# symbol.net
KiCad netlist of a schematic drawn in Altium Designer
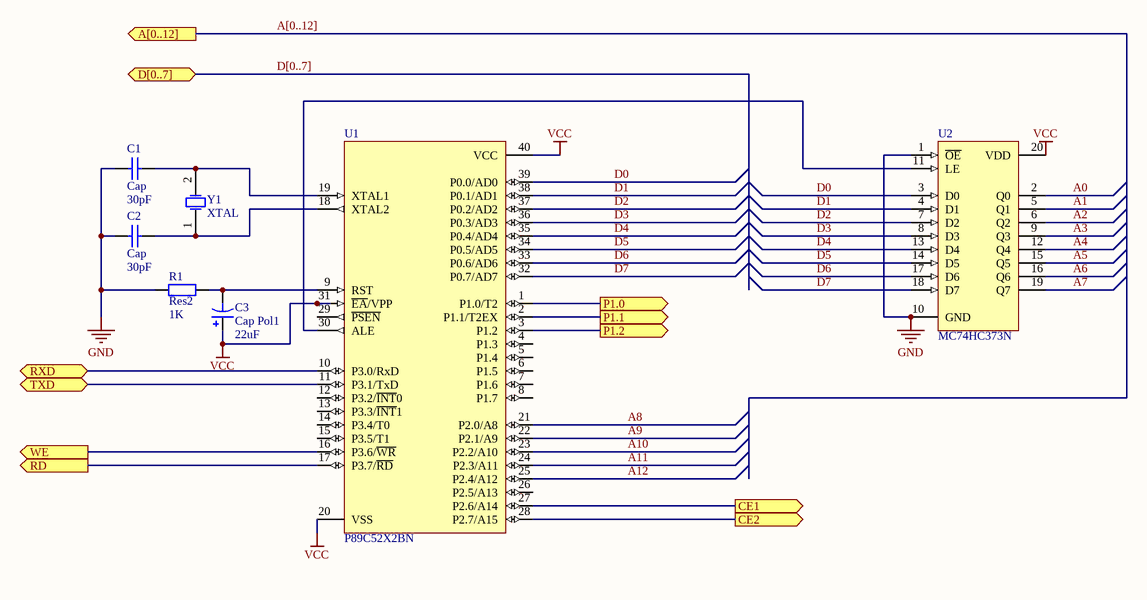
[diagram p0: 单片机系统电路symbol.SchDoc]

(export (version "E")
  (design (tool "Eeschema 10.0.6"))
  (components
    (comp (ref "C1")
      (value "Cap")
      (footprint "RAD-0.3")
      (description "Capacitor")
      (fields (field (name "ALTIUM_VALUE") "30pF") (field (name "PUBLISHER") "Altium Limited"))
      (libsource (lib "Miscellaneous Devices") (part "Cap"))
    )
    (comp (ref "C2")
      (value "Cap")
      (footprint "RAD-0.3")
      (description "Capacitor")
      (fields (field (name "ALTIUM_VALUE") "30pF") (field (name "PUBLISHER") "Altium Limited"))
      (libsource (lib "Miscellaneous Devices") (part "Cap"))
    )
    (comp (ref "C3")
      (value "Cap Pol1")
      (footprint "RB7.6-15")
      (description "Polarized Capacitor (Radial)")
      (fields (field (name "ALTIUM_VALUE") "22uF") (field (name "PUBLISHER") "Altium Limited"))
      (libsource (lib "Miscellaneous Devices") (part "Cap Pol1"))
    )
    (comp (ref "R1")
      (value "Res2")
      (footprint "AXIAL-0.4")
      (description "Resistor")
      (fields (field (name "ALTIUM_VALUE") "1K") (field (name "PUBLISHER") "Altium Limited"))
      (libsource (lib "Miscellaneous Devices") (part "Res2"))
    )
    (comp (ref "U1")
      (value "P89C52X2BN")
      (footprint "SOT129-1")
      (description "80C51 8-Bit Flash Microcontroller Family, 8 kB Flash")
      (fields (field (name "PUBLISHER") "Altium Limited"))
      (libsource (lib "Philips Microcontroller 8-Bit") (part "P89C52X2BN"))
    )
    (comp (ref "U2")
      (value "MC74HC373N")
      (footprint "738-03")
      (description "Octal 3-State Non-Inverting Transparent Latch")
      (fields (field (name "PUBLISHER") "Altium Limited"))
      (libsource (lib "Motorola Logic Latch") (part "MC74HC373N"))
    )
    (comp (ref "Y1")
      (value "XTAL")
      (footprint "R38")
      (description "Crystal Oscillator")
      (fields (field (name "PUBLISHER") "Altium Limited"))
      (libsource (lib "Miscellaneous Devices") (part "XTAL"))
    )
  )
  (nets
    (net (code "1") (name "/A0") (class "Default")
      (node (ref "U2") (pin "2") (pinfunction "Q0_2") (pintype "tri_state"))
    )
    (net (code "2") (name "/A1") (class "Default")
      (node (ref "U2") (pin "5") (pinfunction "Q1_5") (pintype "tri_state"))
    )
    (net (code "3") (name "/A2") (class "Default")
      (node (ref "U2") (pin "6") (pinfunction "Q2_6") (pintype "tri_state"))
    )
    (net (code "4") (name "/A3") (class "Default")
      (node (ref "U2") (pin "9") (pinfunction "Q3_9") (pintype "tri_state"))
    )
    (net (code "5") (name "/A4") (class "Default")
      (node (ref "U2") (pin "12") (pinfunction "Q4_12") (pintype "tri_state"))
    )
    (net (code "6") (name "/A5") (class "Default")
      (node (ref "U2") (pin "15") (pinfunction "Q5_15") (pintype "tri_state"))
    )
    (net (code "7") (name "/A6") (class "Default")
      (node (ref "U2") (pin "16") (pinfunction "Q6_16") (pintype "tri_state"))
    )
    (net (code "8") (name "/A7") (class "Default")
      (node (ref "U2") (pin "19") (pinfunction "Q7_19") (pintype "tri_state"))
    )
    (net (code "9") (name "/A8") (class "Default")
      (node (ref "U1") (pin "21") (pinfunction "P2.0/A8_21") (pintype "bidirectional"))
    )
    (net (code "10") (name "/A9") (class "Default")
      (node (ref "U1") (pin "22") (pinfunction "P2.1/A9_22") (pintype "bidirectional"))
    )
    (net (code "11") (name "/A10") (class "Default")
      (node (ref "U1") (pin "23") (pinfunction "P2.2/A10_23") (pintype "bidirectional"))
    )
    (net (code "12") (name "/A11") (class "Default")
      (node (ref "U1") (pin "24") (pinfunction "P2.3/A11_24") (pintype "bidirectional"))
    )
    (net (code "13") (name "/A12") (class "Default")
      (node (ref "U1") (pin "25") (pinfunction "P2.4/A12_25") (pintype "bidirectional"))
    )
    (net (code "15") (name "/CE1") (class "Default")
      (node (ref "U1") (pin "27") (pinfunction "P2.6/A14_27") (pintype "bidirectional"))
    )
    (net (code "16") (name "/CE2") (class "Default")
      (node (ref "U1") (pin "28") (pinfunction "P2.7/A15_28") (pintype "bidirectional"))
    )
    (net (code "17") (name "/D0") (class "Default")
      (node (ref "U1") (pin "39") (pinfunction "P0.0/AD0_39") (pintype "bidirectional"))
      (node (ref "U2") (pin "3") (pinfunction "D0_3") (pintype "input"))
    )
    (net (code "18") (name "/D1") (class "Default")
      (node (ref "U1") (pin "38") (pinfunction "P0.1/AD1_38") (pintype "bidirectional"))
      (node (ref "U2") (pin "4") (pinfunction "D1_4") (pintype "input"))
    )
    (net (code "19") (name "/D2") (class "Default")
      (node (ref "U1") (pin "37") (pinfunction "P0.2/AD2_37") (pintype "bidirectional"))
      (node (ref "U2") (pin "7") (pinfunction "D2_7") (pintype "input"))
    )
    (net (code "20") (name "/D3") (class "Default")
      (node (ref "U1") (pin "36") (pinfunction "P0.3/AD3_36") (pintype "bidirectional"))
      (node (ref "U2") (pin "8") (pinfunction "D3_8") (pintype "input"))
    )
    (net (code "21") (name "/D4") (class "Default")
      (node (ref "U1") (pin "35") (pinfunction "P0.4/AD4_35") (pintype "bidirectional"))
      (node (ref "U2") (pin "13") (pinfunction "D4_13") (pintype "input"))
    )
    (net (code "22") (name "/D5") (class "Default")
      (node (ref "U1") (pin "34") (pinfunction "P0.5/AD5_34") (pintype "bidirectional"))
      (node (ref "U2") (pin "14") (pinfunction "D5_14") (pintype "input"))
    )
    (net (code "23") (name "/D6") (class "Default")
      (node (ref "U1") (pin "33") (pinfunction "P0.6/AD6_33") (pintype "bidirectional"))
      (node (ref "U2") (pin "17") (pinfunction "D6_17") (pintype "input"))
    )
    (net (code "24") (name "/D7") (class "Default")
      (node (ref "U1") (pin "32") (pinfunction "P0.7/AD7_32") (pintype "bidirectional"))
      (node (ref "U2") (pin "18") (pinfunction "D7_18") (pintype "input"))
    )
    (net (code "26") (name "/P1.0") (class "Default")
      (node (ref "U1") (pin "1") (pinfunction "P1.0/T2_1") (pintype "bidirectional"))
    )
    (net (code "27") (name "/P1.1") (class "Default")
      (node (ref "U1") (pin "2") (pinfunction "P1.1/T2EX_2") (pintype "bidirectional"))
    )
    (net (code "28") (name "/P1.2") (class "Default")
      (node (ref "U1") (pin "3") (pinfunction "P1.2_3") (pintype "bidirectional"))
    )
    (net (code "29") (name "/RD") (class "Default")
      (node (ref "U1") (pin "17") (pinfunction "P3.7/~{RD}_17") (pintype "bidirectional"))
    )
    (net (code "30") (name "/RXD") (class "Default")
      (node (ref "U1") (pin "10") (pinfunction "P3.0/RxD_10") (pintype "bidirectional"))
    )
    (net (code "31") (name "/TXD") (class "Default")
      (node (ref "U1") (pin "11") (pinfunction "P3.1/TxD_11") (pintype "bidirectional"))
    )
    (net (code "32") (name "/WE") (class "Default")
      (node (ref "U1") (pin "16") (pinfunction "P3.6/~{WR}_16") (pintype "bidirectional"))
    )
    (net (code "33") (name "GND") (class "Default")
      (node (ref "C1") (pin "1") (pinfunction "1_1") (pintype "passive"))
      (node (ref "C2") (pin "1") (pinfunction "1_1") (pintype "passive"))
      (node (ref "R1") (pin "1") (pinfunction "1_1") (pintype "passive"))
      (node (ref "U2") (pin "1") (pinfunction "~{OE}_1") (pintype "input"))
      (node (ref "U2") (pin "10") (pinfunction "GND_10") (pintype "power_in"))
    )
    (net (code "34") (name "Net-(U1-ALE)") (class "Default")
      (node (ref "U1") (pin "30") (pinfunction "ALE_30") (pintype "output"))
      (node (ref "U2") (pin "11") (pinfunction "LE_11") (pintype "input"))
    )
    (net (code "35") (name "Net-(U1-RST)") (class "Default")
      (node (ref "C3") (pin "2") (pinfunction "2_2") (pintype "passive"))
      (node (ref "R1") (pin "2") (pinfunction "2_2") (pintype "passive"))
      (node (ref "U1") (pin "9") (pinfunction "RST_9") (pintype "input"))
    )
    (net (code "36") (name "Net-(U1-XTAL1)") (class "Default")
      (node (ref "C1") (pin "2") (pinfunction "2_2") (pintype "passive"))
      (node (ref "U1") (pin "19") (pinfunction "XTAL1_19") (pintype "input"))
      (node (ref "Y1") (pin "2") (pinfunction "OSC2_2") (pintype "passive"))
    )
    (net (code "37") (name "Net-(U1-XTAL2)") (class "Default")
      (node (ref "C2") (pin "2") (pinfunction "2_2") (pintype "passive"))
      (node (ref "U1") (pin "18") (pinfunction "XTAL2_18") (pintype "output"))
      (node (ref "Y1") (pin "1") (pinfunction "OSC1_1") (pintype "passive"))
    )
    (net (code "38") (name "VCC") (class "Default")
      (node (ref "C3") (pin "1") (pinfunction "1_1") (pintype "passive"))
      (node (ref "U1") (pin "20") (pinfunction "VSS_20") (pintype "power_in"))
      (node (ref "U1") (pin "31") (pinfunction "~{EA}/VPP_31") (pintype "input"))
      (node (ref "U1") (pin "40") (pinfunction "VCC_40") (pintype "power_in"))
      (node (ref "U2") (pin "20") (pinfunction "VDD_20") (pintype "power_in"))
    )
    (net (code "39") (name "unconnected-(U1-P1.3-Pad4)") (class "Default")
      (node (ref "U1") (pin "4") (pinfunction "P1.3_4") (pintype "bidirectional"))
    )
    (net (code "40") (name "unconnected-(U1-P1.4-Pad5)") (class "Default")
      (node (ref "U1") (pin "5") (pinfunction "P1.4_5") (pintype "bidirectional"))
    )
    (net (code "41") (name "unconnected-(U1-P1.5-Pad6)") (class "Default")
      (node (ref "U1") (pin "6") (pinfunction "P1.5_6") (pintype "bidirectional"))
    )
    (net (code "42") (name "unconnected-(U1-P1.6-Pad7)") (class "Default")
      (node (ref "U1") (pin "7") (pinfunction "P1.6_7") (pintype "bidirectional"))
    )
    (net (code "43") (name "unconnected-(U1-P1.7-Pad8)") (class "Default")
      (node (ref "U1") (pin "8") (pinfunction "P1.7_8") (pintype "bidirectional"))
    )
    (net (code "44") (name "unconnected-(U1-P2.5{slash}A13-Pad26)") (class "Default")
      (node (ref "U1") (pin "26") (pinfunction "P2.5/A13_26") (pintype "bidirectional"))
    )
    (net (code "45") (name "unconnected-(U1-P3.2{slash}~{INT}0-Pad12)") (class "Default")
      (node (ref "U1") (pin "12") (pinfunction "P3.2/~{INT}0_12") (pintype "bidirectional"))
    )
    (net (code "46") (name "unconnected-(U1-P3.3{slash}~{INT}1-Pad13)") (class "Default")
      (node (ref "U1") (pin "13") (pinfunction "P3.3/~{INT}1_13") (pintype "bidirectional"))
    )
    (net (code "47") (name "unconnected-(U1-P3.4{slash}T0-Pad14)") (class "Default")
      (node (ref "U1") (pin "14") (pinfunction "P3.4/T0_14") (pintype "bidirectional"))
    )
    (net (code "48") (name "unconnected-(U1-P3.5{slash}T1-Pad15)") (class "Default")
      (node (ref "U1") (pin "15") (pinfunction "P3.5/T1_15") (pintype "bidirectional"))
    )
    (net (code "49") (name "unconnected-(U1-~{PSEN}-Pad29)") (class "Default")
      (node (ref "U1") (pin "29") (pinfunction "~{PSEN}_29") (pintype "output"))
    )
  )
)
